# Power.net
KiCad netlist of a schematic drawn in Altium Designer
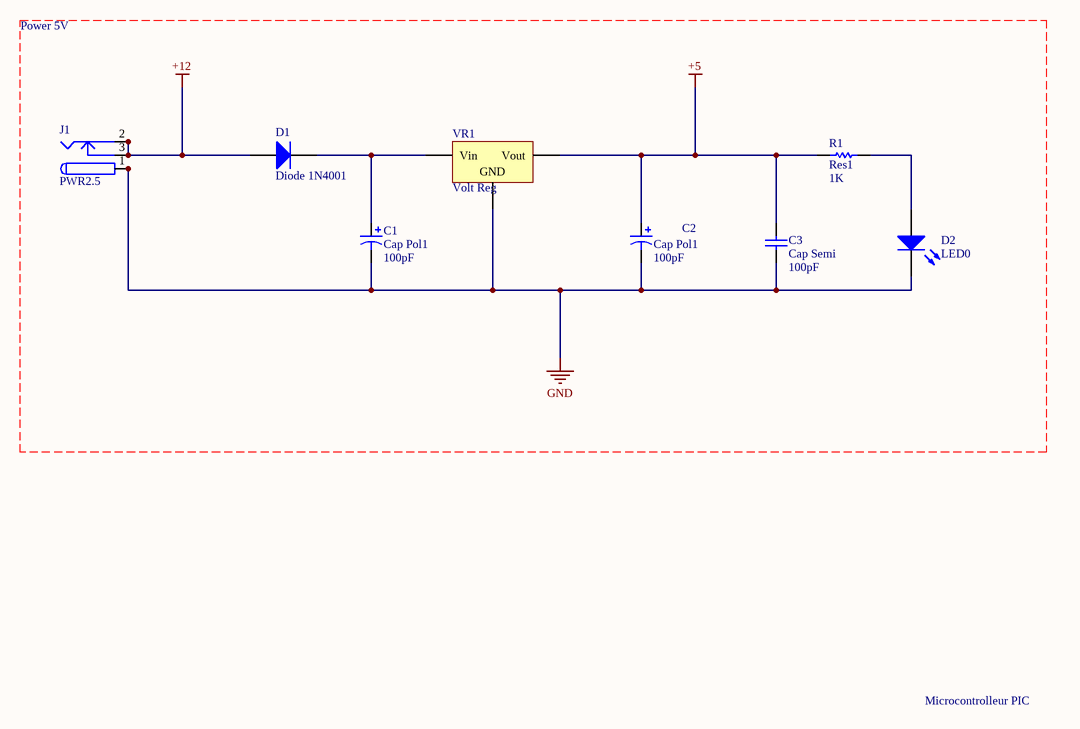
[diagram p0: Power.SchDoc]

(export (version "E")
  (design (tool "Eeschema 10.0.6"))
  (components
    (comp (ref "C1")
      (value "Cap Pol1")
      (footprint "RB7.6-15")
      (description "Polarized Capacitor (Radial)")
      (fields (field (name "ALTIUM_VALUE") "100pF") (field (name "PUBLISHER") "Altium Limited"))
      (libsource (lib "Miscellaneous Devices") (part "Cap Pol1"))
    )
    (comp (ref "C2")
      (value "Cap Pol1")
      (footprint "RB7.6-15")
      (description "Polarized Capacitor (Radial)")
      (fields (field (name "ALTIUM_VALUE") "100pF") (field (name "PUBLISHER") "Altium Limited"))
      (libsource (lib "Miscellaneous Devices") (part "Cap Pol1"))
    )
    (comp (ref "C3")
      (value "Cap Semi")
      (footprint "C1206")
      (description "Capacitor (Semiconductor SIM Model)")
      (fields (field (name "ALTIUM_VALUE") "100pF") (field (name "PUBLISHER") "Altium Limited"))
      (libsource (lib "Miscellaneous Devices") (part "Cap Semi"))
    )
    (comp (ref "D1")
      (value "Diode 1N4001")
      (footprint "DO-41")
      (description "1 Amp General Purpose Rectifier")
      (fields (field (name "PUBLISHER") "Altium Limited"))
      (libsource (lib "Miscellaneous Devices") (part "Diode 1N4001"))
    )
    (comp (ref "D2")
      (value "LED0")
      (footprint "LED-0")
      (description "Typical INFRARED GaAs LED")
      (fields (field (name "PUBLISHER") "Altium Limited"))
      (libsource (lib "Miscellaneous Devices") (part "LED0"))
    )
    (comp (ref "J1")
      (value "PWR2.5")
      (footprint "KLD-0202")
      (description "Low Voltage Power Supply Connector")
      (fields (field (name "PUBLISHER") "Altium Limited"))
      (libsource (lib "Miscellaneous Connectors") (part "PWR2.5"))
    )
    (comp (ref "R1")
      (value "Res1")
      (footprint "AXIAL-0.3")
      (description "Resistor")
      (fields (field (name "ALTIUM_VALUE") "1K") (field (name "PUBLISHER") "Altium Limited"))
      (libsource (lib "Miscellaneous Devices") (part "Res1"))
    )
    (comp (ref "VR1")
      (value "Volt Reg")
      (footprint "D2PAK_N")
      (description "Voltage Regulator")
      (fields (field (name "PUBLISHER") "Altium Limited"))
      (libsource (lib "Miscellaneous Devices") (part "Volt Reg"))
    )
  )
  (nets
    (net (code "1") (name "+5") (class "Default")
      (node (ref "C2") (pin "1") (pinfunction "1_1") (pintype "passive"))
      (node (ref "C3") (pin "2") (pinfunction "2_2") (pintype "passive"))
      (node (ref "R1") (pin "1") (pinfunction "1_1") (pintype "passive"))
      (node (ref "VR1") (pin "3") (pinfunction "Vout_3") (pintype "passive"))
    )
    (net (code "2") (name "+12") (class "Default")
      (node (ref "D1") (pin "1") (pinfunction "A_1") (pintype "passive"))
      (node (ref "J1") (pin "2") (pinfunction "2_2") (pintype "power_in"))
      (node (ref "J1") (pin "2A") (pinfunction "2A_2A") (pintype "power_in"))
      (node (ref "J1") (pin "2B") (pinfunction "2B_2B") (pintype "power_in"))
      (node (ref "J1") (pin "3") (pinfunction "3_3") (pintype "power_in"))
      (node (ref "J1") (pin "3A") (pinfunction "3A_3A") (pintype "power_in"))
      (node (ref "J1") (pin "3B") (pinfunction "3B_3B") (pintype "power_in"))
    )
    (net (code "3") (name "GND") (class "Default")
      (node (ref "C1") (pin "2") (pinfunction "2_2") (pintype "passive"))
      (node (ref "C2") (pin "2") (pinfunction "2_2") (pintype "passive"))
      (node (ref "C3") (pin "1") (pinfunction "1_1") (pintype "passive"))
      (node (ref "D2") (pin "2") (pinfunction "K_2") (pintype "passive"))
      (node (ref "J1") (pin "1") (pinfunction "1_1") (pintype "power_in"))
      (node (ref "J1") (pin "1A") (pinfunction "1A_1A") (pintype "power_in"))
      (node (ref "J1") (pin "1B") (pinfunction "1B_1B") (pintype "power_in"))
      (node (ref "VR1") (pin "2") (pinfunction "GND_2") (pintype "passive"))
    )
    (net (code "4") (name "Net-(D1-K)") (class "Default")
      (node (ref "C1") (pin "1") (pinfunction "1_1") (pintype "passive"))
      (node (ref "D1") (pin "2") (pinfunction "K_2") (pintype "passive"))
      (node (ref "VR1") (pin "1") (pinfunction "Vin_1") (pintype "passive"))
    )
    (net (code "5") (name "Net-(D2-A)") (class "Default")
      (node (ref "D2") (pin "1") (pinfunction "A_1") (pintype "passive"))
      (node (ref "R1") (pin "2") (pinfunction "2_2") (pintype "passive"))
    )
  )
)
